# Sheet2.net
KiCad netlist of a schematic drawn in Altium Designer
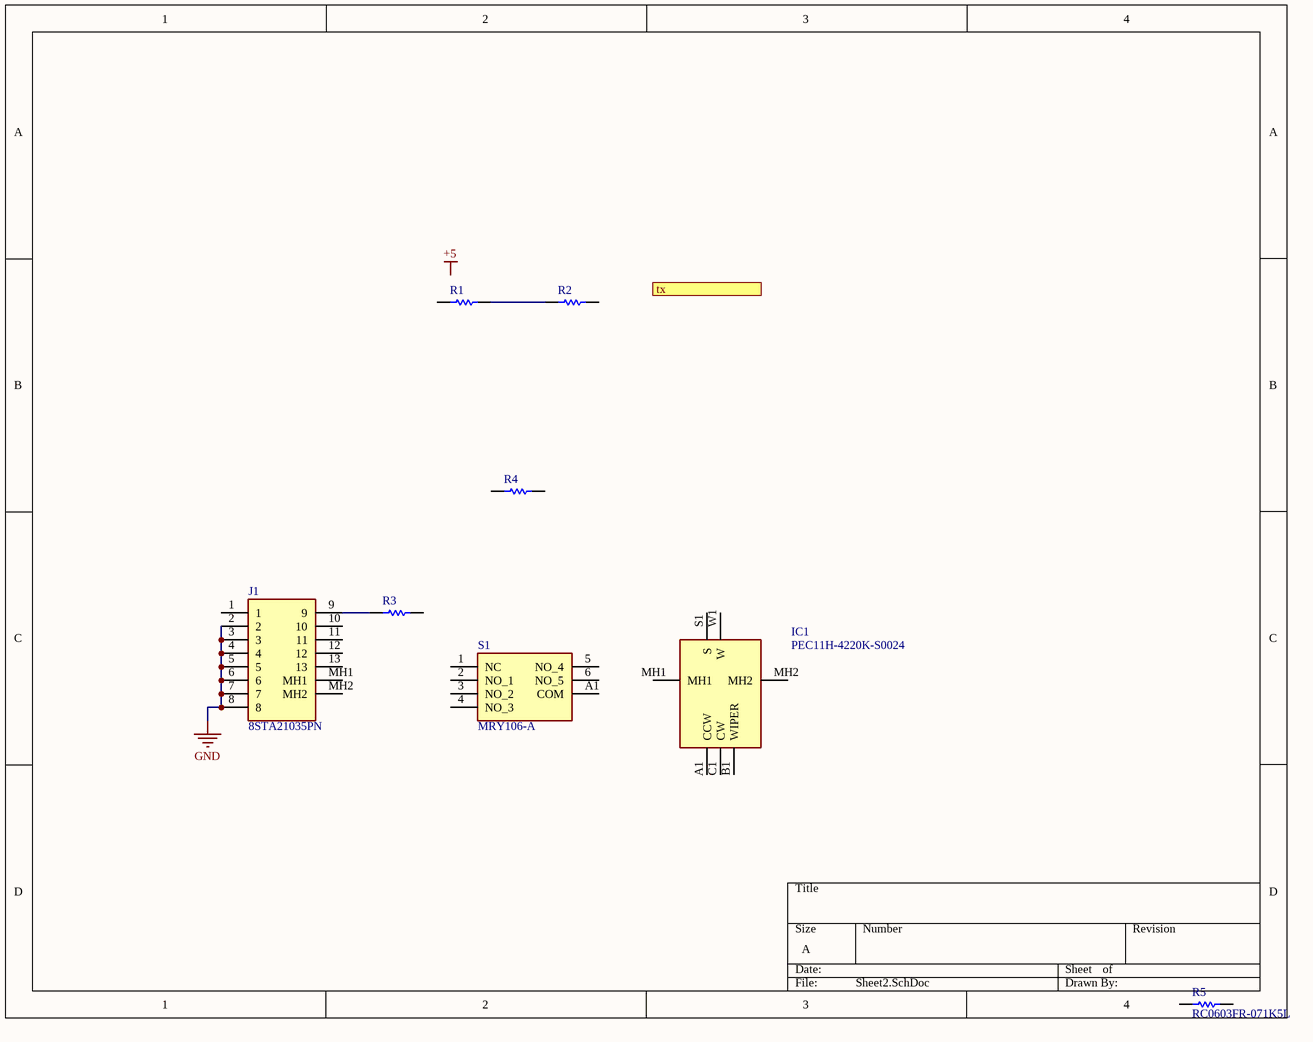
[diagram p0: Sheet2.SchDoc]

(export (version "E")
  (design (tool "Eeschema 10.0.6"))
  (components
    (comp (ref "IC1")
      (value "PEC11H-4220K-S0024")
      (footprint "SamacSys:PEC11H4220KS0024")
      (description "Integrated Circuit")
      (fields (field (name "MOUSER PART NUMBER") "652-PEC11H4220KS0024"))
      (libsource (lib "*") (part "PEC11H-4220K-S0024"))
    )
    (comp (ref "J1")
      (value "8STA21035PN")
      (footprint "SamacSys:8STA21035PN")
      (description "Connector")
      (libsource (lib "*") (part "8STA21035PN"))
    )
    (comp (ref "R1")
      (value "RC0603FR-071K5L")
      (footprint "RESC1608X55X25ML10T15")
      (description "Chip Resistor, 1.5 KOhm, +/- 1%, 0.1 W, -55 to 155 degC, 0603 (1608 Metric), RoHS, Tape and Reel")
      (fields (field (name "TOLERANCE") "1%") (field (name "MANUFACTURER") "Yageo"))
      (libsource (lib "Altium Content Vault") (part "RES-2"))
    )
    (comp (ref "R2")
      (value "RC0603FR-071K5L")
      (footprint "RESC1608X55X25ML10T15")
      (description "Chip Resistor, 1.5 KOhm, +/- 1%, 0.1 W, -55 to 155 degC, 0603 (1608 Metric), RoHS, Tape and Reel")
      (fields (field (name "TOLERANCE") "1%") (field (name "MANUFACTURER") "Yageo"))
      (libsource (lib "Altium Content Vault") (part "RES-2"))
    )
    (comp (ref "R3")
      (value "RC0603FR-071K5L")
      (footprint "RESC1608X55X25ML10T15")
      (description "Chip Resistor, 1.5 KOhm, +/- 1%, 0.1 W, -55 to 155 degC, 0603 (1608 Metric), RoHS, Tape and Reel")
      (fields (field (name "TOLERANCE") "1%") (field (name "MANUFACTURER") "Yageo"))
      (libsource (lib "Altium Content Vault") (part "RES-2"))
    )
    (comp (ref "R4")
      (value "RC0603FR-071K5L")
      (footprint "RESC1608X55X25ML10T15")
      (description "Chip Resistor, 1.5 KOhm, +/- 1%, 0.1 W, -55 to 155 degC, 0603 (1608 Metric), RoHS, Tape and Reel")
      (fields (field (name "TOLERANCE") "1%") (field (name "MANUFACTURER") "Yageo"))
      (libsource (lib "Altium Content Vault") (part "RES-2"))
    )
    (comp (ref "R5")
      (value "RC0603FR-071K5L")
      (footprint "RESC1608X55X25ML10T15")
      (description "Chip Resistor, 1.5 KOhm, +/- 1%, 0.1 W, -55 to 155 degC, 0603 (1608 Metric), RoHS, Tape and Reel")
      (fields (field (name "TOLERANCE") "1%") (field (name "MANUFACTURER") "Yageo"))
      (libsource (lib "Altium Content Vault") (part "RES-2"))
    )
    (comp (ref "S1")
      (value "MRY106-A")
      (footprint "SamacSys:MRY106A")
      (description "Switch")
      (fields (field (name "MOUSER PART NUMBER") "633-MRY106A"))
      (libsource (lib "*") (part "MRY106-A"))
    )
  )
  (nets
    (net (code "3") (name "GND") (class "Default")
      (node (ref "J1") (pin "2") (pinfunction "2_2") (pintype "passive"))
      (node (ref "J1") (pin "3") (pinfunction "3_3") (pintype "passive"))
      (node (ref "J1") (pin "4") (pinfunction "4_4") (pintype "passive"))
      (node (ref "J1") (pin "5") (pinfunction "5_5") (pintype "passive"))
      (node (ref "J1") (pin "6") (pinfunction "6_6") (pintype "passive"))
      (node (ref "J1") (pin "7") (pinfunction "7_7") (pintype "passive"))
      (node (ref "J1") (pin "8") (pinfunction "8_8") (pintype "passive"))
    )
    (net (code "4") (name "Net-(J1-Pad9)") (class "Default")
      (node (ref "J1") (pin "9") (pinfunction "9_9") (pintype "passive"))
      (node (ref "R3") (pin "1") (pinfunction "1_1") (pintype "passive"))
    )
    (net (code "5") (name "Net-(R1-Pad2)") (class "Default")
      (node (ref "R1") (pin "2") (pinfunction "2_2") (pintype "passive"))
      (node (ref "R2") (pin "1") (pinfunction "1_1") (pintype "passive"))
    )
    (net (code "6") (name "unconnected-(IC1-CCW-PadA1)") (class "Default")
      (node (ref "IC1") (pin "A1") (pinfunction "CCW_A1") (pintype "passive"))
    )
    (net (code "7") (name "unconnected-(IC1-CW-PadC1)") (class "Default")
      (node (ref "IC1") (pin "C1") (pinfunction "CW_C1") (pintype "passive"))
    )
    (net (code "8") (name "unconnected-(IC1-PadMH1)") (class "Default")
      (node (ref "IC1") (pin "MH1") (pinfunction "MH1_MH1") (pintype "passive"))
    )
    (net (code "9") (name "unconnected-(IC1-PadMH2)") (class "Default")
      (node (ref "IC1") (pin "MH2") (pinfunction "MH2_MH2") (pintype "passive"))
    )
    (net (code "10") (name "unconnected-(IC1-S-PadS1)") (class "Default")
      (node (ref "IC1") (pin "S1") (pinfunction "S_S1") (pintype "passive"))
    )
    (net (code "11") (name "unconnected-(IC1-W-PadW1)") (class "Default")
      (node (ref "IC1") (pin "W1") (pinfunction "W_W1") (pintype "passive"))
    )
    (net (code "12") (name "unconnected-(IC1-WIPER-PadB1)") (class "Default")
      (node (ref "IC1") (pin "B1") (pinfunction "WIPER_B1") (pintype "passive"))
    )
    (net (code "13") (name "unconnected-(J1-Pad1)") (class "Default")
      (node (ref "J1") (pin "1") (pinfunction "1_1") (pintype "passive"))
    )
    (net (code "14") (name "unconnected-(J1-Pad10)") (class "Default")
      (node (ref "J1") (pin "10") (pinfunction "10_10") (pintype "passive"))
    )
    (net (code "15") (name "unconnected-(J1-Pad11)") (class "Default")
      (node (ref "J1") (pin "11") (pinfunction "11_11") (pintype "passive"))
    )
    (net (code "16") (name "unconnected-(J1-Pad12)") (class "Default")
      (node (ref "J1") (pin "12") (pinfunction "12_12") (pintype "passive"))
    )
    (net (code "17") (name "unconnected-(J1-Pad13)") (class "Default")
      (node (ref "J1") (pin "13") (pinfunction "13_13") (pintype "passive"))
    )
    (net (code "18") (name "unconnected-(J1-PadMH1)") (class "Default")
      (node (ref "J1") (pin "MH1") (pinfunction "MH1_MH1") (pintype "passive"))
    )
    (net (code "19") (name "unconnected-(J1-PadMH2)") (class "Default")
      (node (ref "J1") (pin "MH2") (pinfunction "MH2_MH2") (pintype "passive"))
    )
    (net (code "20") (name "unconnected-(R1-Pad1)") (class "Default")
      (node (ref "R1") (pin "1") (pinfunction "1_1") (pintype "passive"))
    )
    (net (code "21") (name "unconnected-(R2-Pad2)") (class "Default")
      (node (ref "R2") (pin "2") (pinfunction "2_2") (pintype "passive"))
    )
    (net (code "22") (name "unconnected-(R3-Pad2)") (class "Default")
      (node (ref "R3") (pin "2") (pinfunction "2_2") (pintype "passive"))
    )
    (net (code "23") (name "unconnected-(R4-Pad1)") (class "Default")
      (node (ref "R4") (pin "1") (pinfunction "1_1") (pintype "passive"))
    )
    (net (code "24") (name "unconnected-(R4-Pad2)") (class "Default")
      (node (ref "R4") (pin "2") (pinfunction "2_2") (pintype "passive"))
    )
    (net (code "25") (name "unconnected-(R5-Pad1)") (class "Default")
      (node (ref "R5") (pin "1") (pinfunction "1_1") (pintype "passive"))
    )
    (net (code "26") (name "unconnected-(R5-Pad2)") (class "Default")
      (node (ref "R5") (pin "2") (pinfunction "2_2") (pintype "passive"))
    )
    (net (code "27") (name "unconnected-(S1-COM-PadA1)") (class "Default")
      (node (ref "S1") (pin "A1") (pinfunction "COM_A1") (pintype "passive"))
    )
    (net (code "28") (name "unconnected-(S1-NC-Pad1)") (class "Default")
      (node (ref "S1") (pin "1") (pinfunction "NC_1") (pintype "passive"))
    )
    (net (code "29") (name "unconnected-(S1-NO_1-Pad2)") (class "Default")
      (node (ref "S1") (pin "2") (pinfunction "NO_1_2") (pintype "passive"))
    )
    (net (code "30") (name "unconnected-(S1-NO_2-Pad3)") (class "Default")
      (node (ref "S1") (pin "3") (pinfunction "NO_2_3") (pintype "passive"))
    )
    (net (code "31") (name "unconnected-(S1-NO_3-Pad4)") (class "Default")
      (node (ref "S1") (pin "4") (pinfunction "NO_3_4") (pintype "passive"))
    )
    (net (code "32") (name "unconnected-(S1-NO_4-Pad5)") (class "Default")
      (node (ref "S1") (pin "5") (pinfunction "NO_4_5") (pintype "passive"))
    )
    (net (code "33") (name "unconnected-(S1-NO_5-Pad6)") (class "Default")
      (node (ref "S1") (pin "6") (pinfunction "NO_5_6") (pintype "passive"))
    )
  )
)
